# Configuration_Logic.net
KiCad netlist of a schematic drawn in Altium Designer
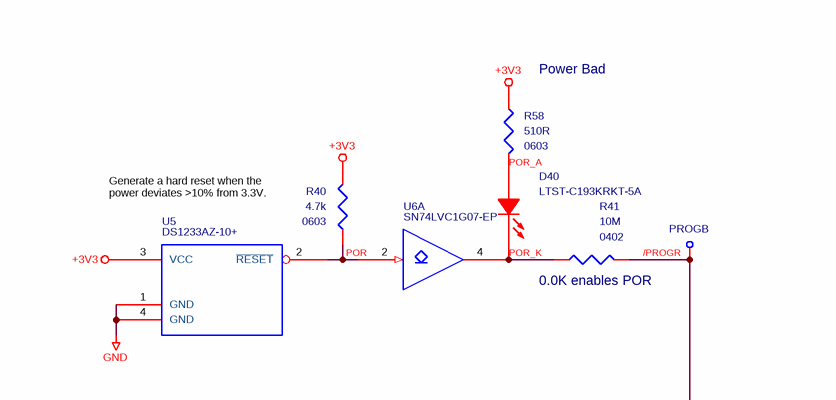
[diagram p0: Configuration_Logic.SchDoc, top left]
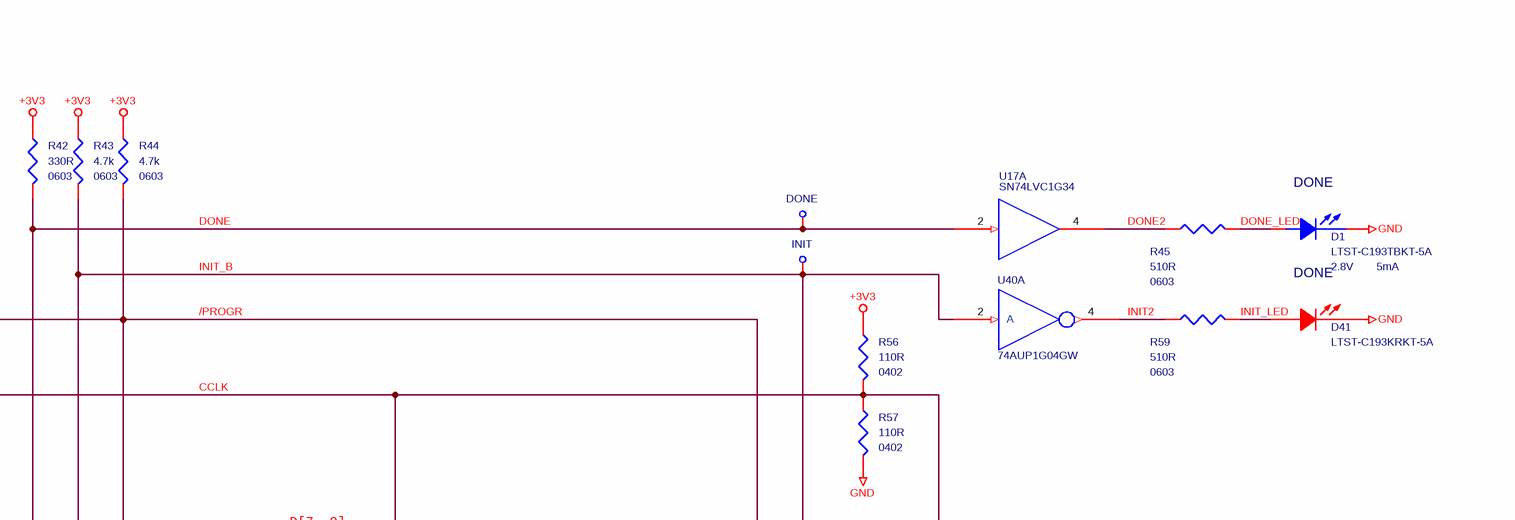
[diagram p1: Configuration_Logic.SchDoc, top right]
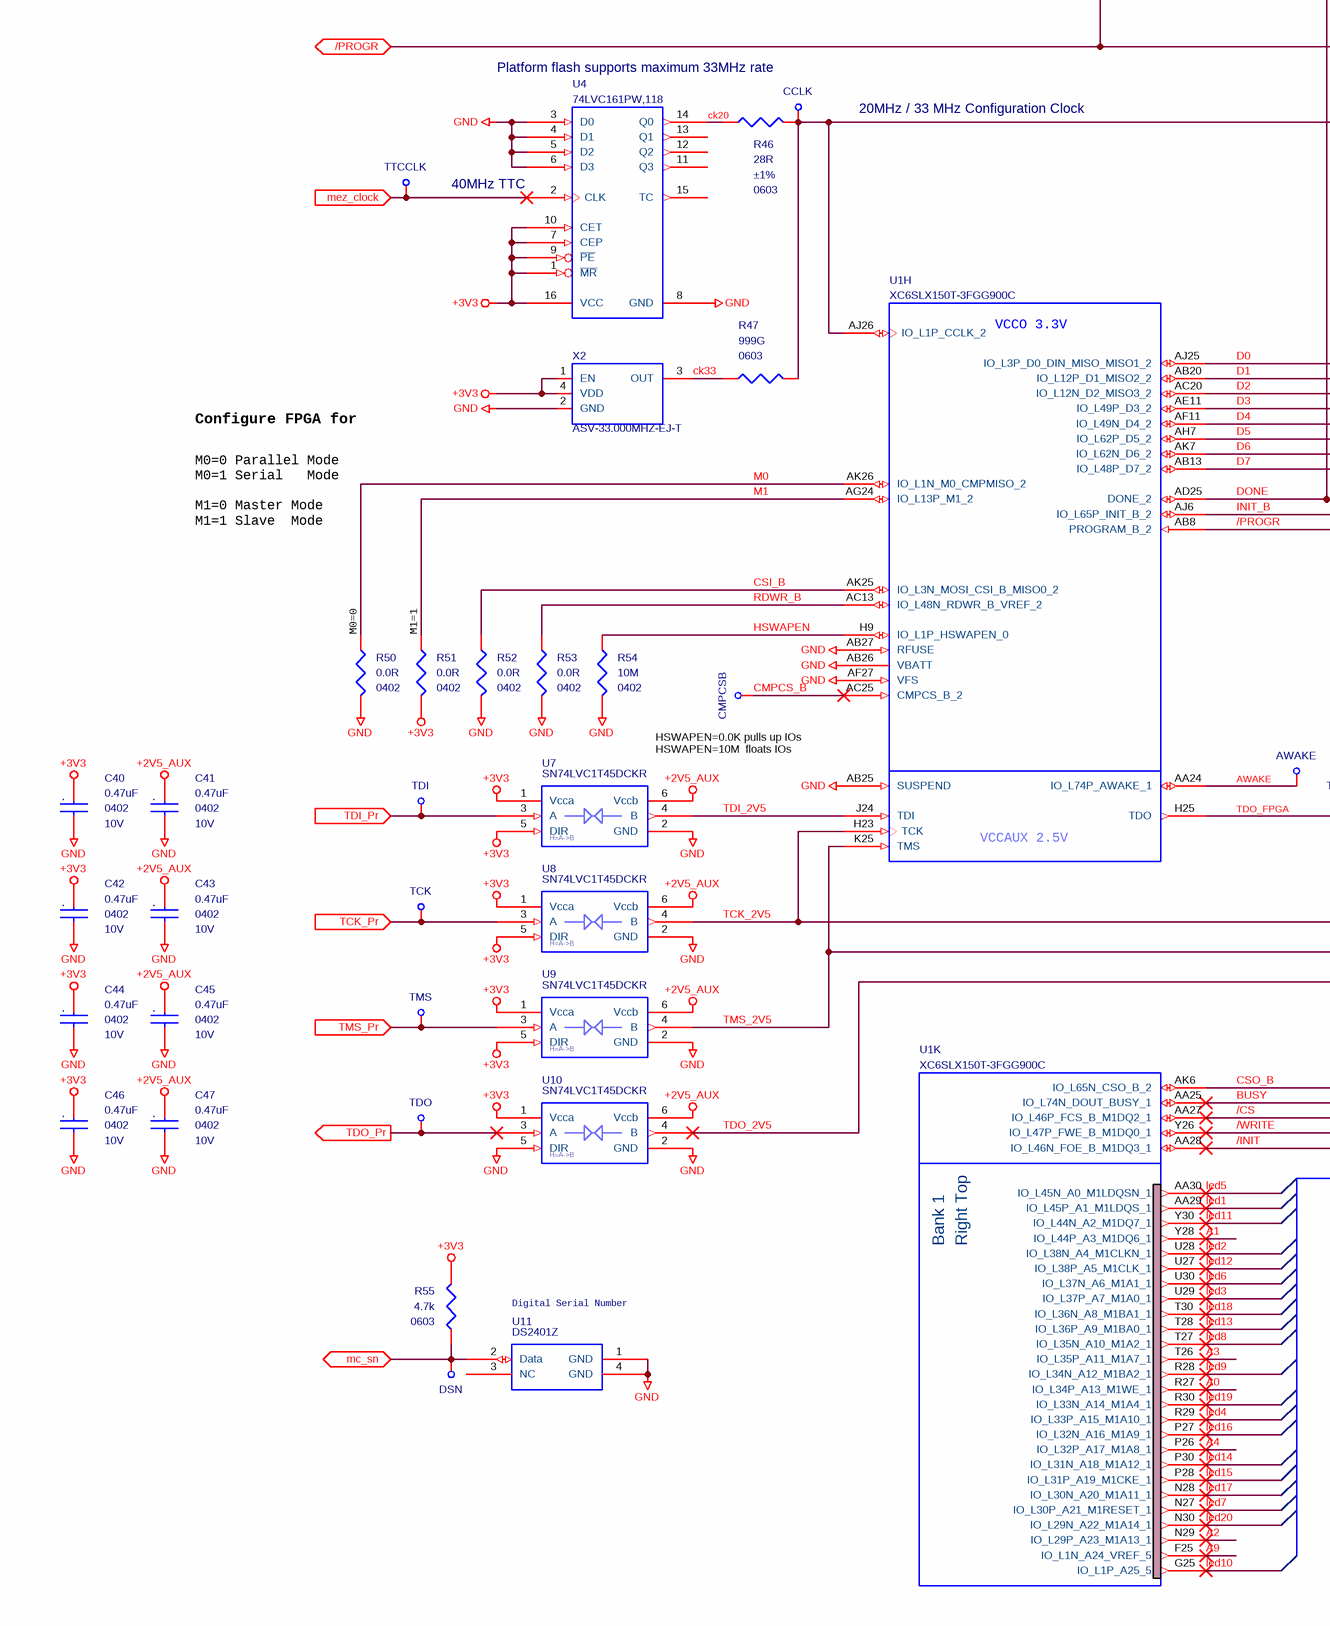
[diagram p2: Configuration_Logic.SchDoc, bottom left]
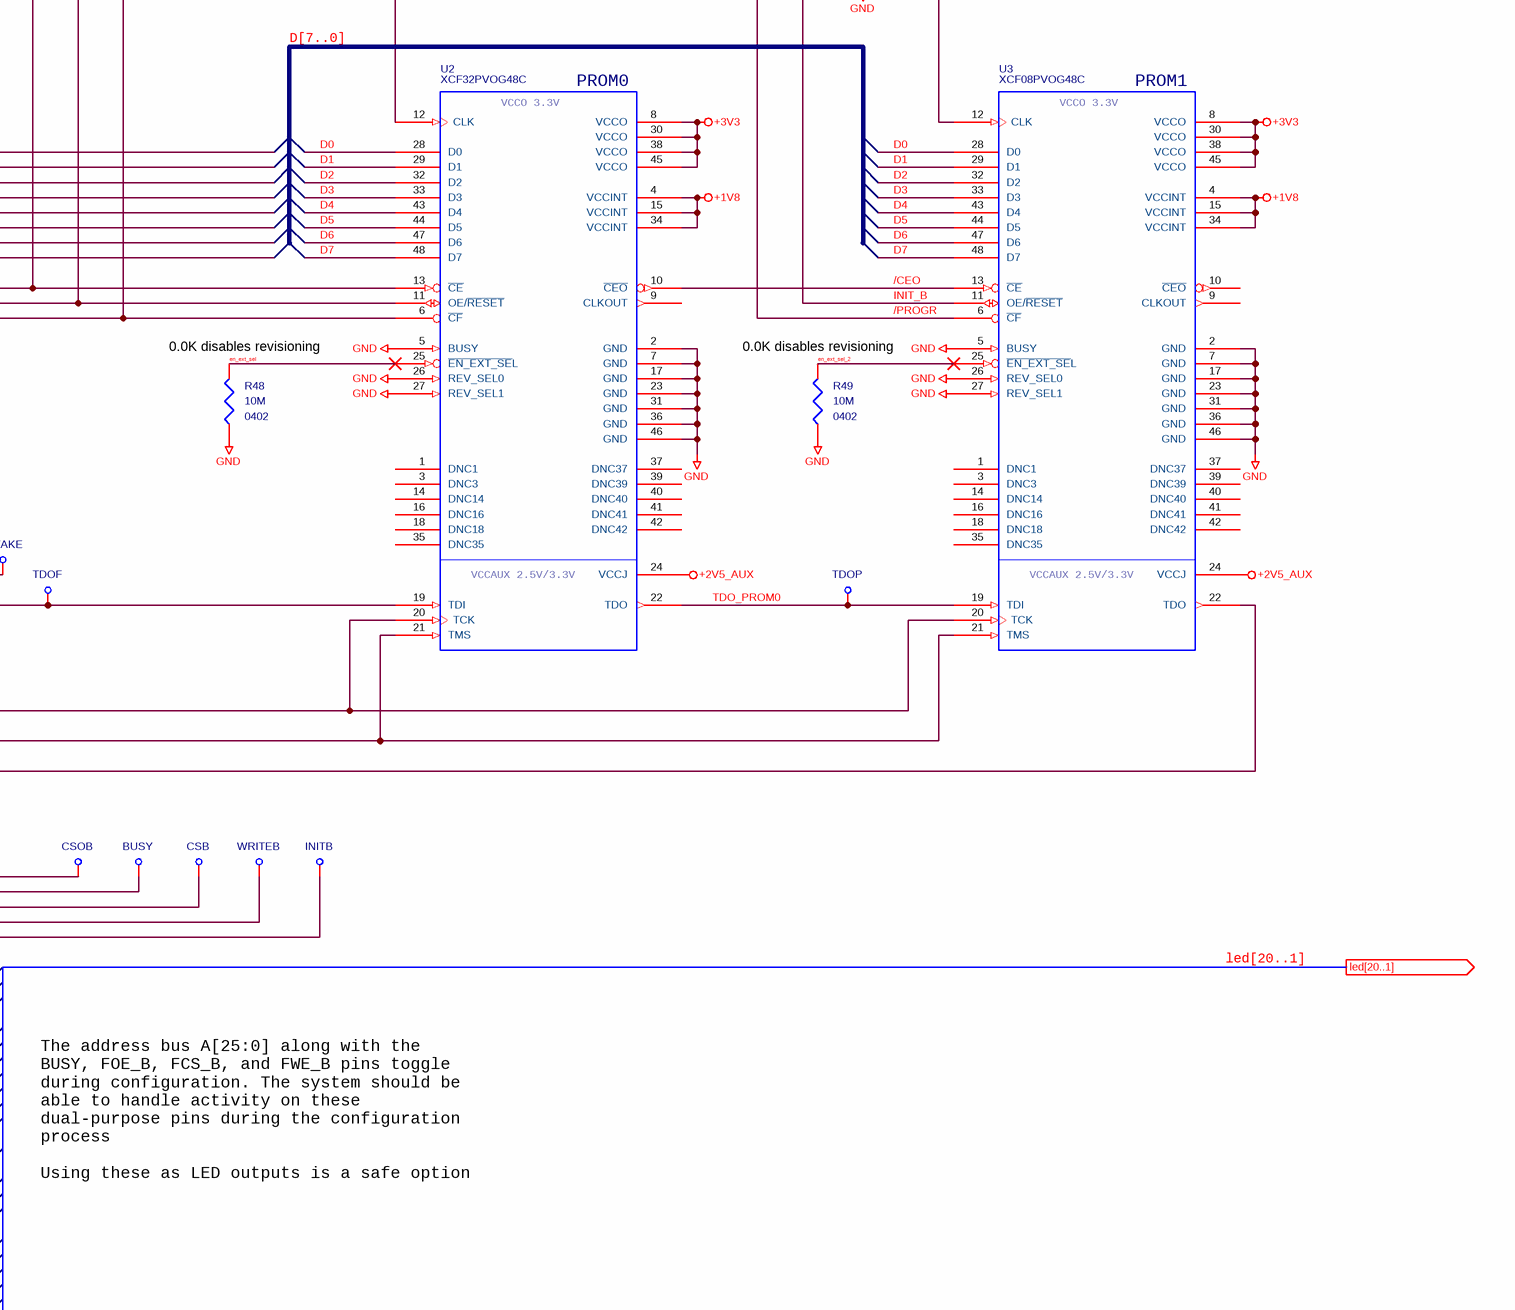
[diagram p3: Configuration_Logic.SchDoc, bottom right]

(export (version "E")
  (design (tool "Eeschema 10.0.6"))
  (components
    (comp (ref "AWAKE")
      (value "Test Point Via")
      (footprint "MC_S6/TH/TPVIA")
      (libsource (lib "ALCT_MEZ_SPARTAN6_Library") (part "TPVIA"))
    )
    (comp (ref "BUSY")
      (value "Test Point Via")
      (footprint "MC_S6/TH/TPVIA")
      (libsource (lib "ALCT_MEZ_SPARTAN6_Library") (part "TPVIA"))
    )
    (comp (ref "C40")
      (value "0.47uF")
      (footprint "MC_S6/SM/C_0402_IPC")
      (description "CAP CER 0.47UF 10V X5R 0402")
      (fields
        (field (name "MANUFACTURER") "Murata Electronics North America")
        (field (name "MANUFACTURER PART NUMBER") "GRM155R61A474KE15J")
        (field (name "VOLTAGE - RATED") "10V")
        (field (name "PACKAGE") "0402")
      )
      (libsource (lib "ALCT_MEZ_SPARTAN6_Library") (part "GRM155R61A474KE15J"))
    )
    (comp (ref "C41")
      (value "0.47uF")
      (footprint "MC_S6/SM/C_0402_IPC")
      (description "CAP CER 0.47UF 10V X5R 0402")
      (fields
        (field (name "MANUFACTURER") "Murata Electronics North America")
        (field (name "MANUFACTURER PART NUMBER") "GRM155R61A474KE15J")
        (field (name "VOLTAGE - RATED") "10V")
        (field (name "PACKAGE") "0402")
      )
      (libsource (lib "ALCT_MEZ_SPARTAN6_Library") (part "GRM155R61A474KE15J"))
    )
    (comp (ref "C42")
      (value "0.47uF")
      (footprint "MC_S6/SM/C_0402_IPC")
      (description "CAP CER 0.47UF 10V X5R 0402")
      (fields
        (field (name "MANUFACTURER") "Murata Electronics North America")
        (field (name "MANUFACTURER PART NUMBER") "GRM155R61A474KE15J")
        (field (name "VOLTAGE - RATED") "10V")
        (field (name "PACKAGE") "0402")
      )
      (libsource (lib "ALCT_MEZ_SPARTAN6_Library") (part "GRM155R61A474KE15J"))
    )
    (comp (ref "C43")
      (value "0.47uF")
      (footprint "MC_S6/SM/C_0402_IPC")
      (description "CAP CER 0.47UF 10V X5R 0402")
      (fields
        (field (name "MANUFACTURER") "Murata Electronics North America")
        (field (name "MANUFACTURER PART NUMBER") "GRM155R61A474KE15J")
        (field (name "VOLTAGE - RATED") "10V")
        (field (name "PACKAGE") "0402")
      )
      (libsource (lib "ALCT_MEZ_SPARTAN6_Library") (part "GRM155R61A474KE15J"))
    )
    (comp (ref "C44")
      (value "0.47uF")
      (footprint "MC_S6/SM/C_0402_IPC")
      (description "CAP CER 0.47UF 10V X5R 0402")
      (fields
        (field (name "MANUFACTURER") "Murata Electronics North America")
        (field (name "MANUFACTURER PART NUMBER") "GRM155R61A474KE15J")
        (field (name "VOLTAGE - RATED") "10V")
        (field (name "PACKAGE") "0402")
      )
      (libsource (lib "ALCT_MEZ_SPARTAN6_Library") (part "GRM155R61A474KE15J"))
    )
    (comp (ref "C45")
      (value "0.47uF")
      (footprint "MC_S6/SM/C_0402_IPC")
      (description "CAP CER 0.47UF 10V X5R 0402")
      (fields
        (field (name "MANUFACTURER") "Murata Electronics North America")
        (field (name "MANUFACTURER PART NUMBER") "GRM155R61A474KE15J")
        (field (name "VOLTAGE - RATED") "10V")
        (field (name "PACKAGE") "0402")
      )
      (libsource (lib "ALCT_MEZ_SPARTAN6_Library") (part "GRM155R61A474KE15J"))
    )
    (comp (ref "C46")
      (value "0.47uF")
      (footprint "MC_S6/SM/C_0402_IPC")
      (description "CAP CER 0.47UF 10V X5R 0402")
      (fields
        (field (name "MANUFACTURER") "Murata Electronics North America")
        (field (name "MANUFACTURER PART NUMBER") "GRM155R61A474KE15J")
        (field (name "VOLTAGE - RATED") "10V")
        (field (name "PACKAGE") "0402")
      )
      (libsource (lib "ALCT_MEZ_SPARTAN6_Library") (part "GRM155R61A474KE15J"))
    )
    (comp (ref "C47")
      (value "0.47uF")
      (footprint "MC_S6/SM/C_0402_IPC")
      (description "CAP CER 0.47UF 10V X5R 0402")
      (fields
        (field (name "MANUFACTURER") "Murata Electronics North America")
        (field (name "MANUFACTURER PART NUMBER") "GRM155R61A474KE15J")
        (field (name "VOLTAGE - RATED") "10V")
        (field (name "PACKAGE") "0402")
      )
      (libsource (lib "ALCT_MEZ_SPARTAN6_Library") (part "GRM155R61A474KE15J"))
    )
    (comp (ref "CCLK")
      (value "Test Point Via")
      (footprint "MC_S6/TH/TPVIA")
      (libsource (lib "ALCT_MEZ_SPARTAN6_Library") (part "TPVIA"))
    )
    (comp (ref "CMPCSB")
      (value "Test Point Via")
      (footprint "MC_S6/TH/TPVIA")
      (libsource (lib "ALCT_MEZ_SPARTAN6_Library") (part "TPVIA"))
    )
    (comp (ref "CSB")
      (value "Test Point Via")
      (footprint "MC_S6/TH/TPVIA")
      (libsource (lib "ALCT_MEZ_SPARTAN6_Library") (part "TPVIA"))
    )
    (comp (ref "CSOB")
      (value "Test Point Via")
      (footprint "MC_S6/TH/TPVIA")
      (libsource (lib "ALCT_MEZ_SPARTAN6_Library") (part "TPVIA"))
    )
    (comp (ref "D1")
      (value "LTST-C193TBKT-5A")
      (footprint "MC_S6/SM/LED_0603")
      (description "LED BLUE CLEAR 0603 SMD")
      (fields
        (field (name "MANUFACTURER") "Lite-On Inc.")
        (field (name "VOLTAGE - FORWARD (VF) (TYP)") "2.8V")
        (field (name "CURRENT - TEST") "5mA")
      )
      (libsource (lib "ALCT_MEZ_SPARTAN6_Library") (part "LTST-C193TBKT-5A"))
    )
    (comp (ref "D40")
      (value "LTST-C193KRKT-5A")
      (footprint "MC_S6/SM/LED_0603")
      (description "LED RED CLEAR 0603 SMD")
      (fields (field (name "MANUFACTURER") "Lite-On Inc."))
      (libsource (lib "ALCT_MEZ_SPARTAN6_Library") (part "LTST-C193KRKT-5A"))
    )
    (comp (ref "D41")
      (value "LTST-C193KRKT-5A")
      (footprint "MC_S6/SM/LED_0603")
      (description "LED RED CLEAR 0603 SMD")
      (fields (field (name "MANUFACTURER") "Lite-On Inc."))
      (libsource (lib "ALCT_MEZ_SPARTAN6_Library") (part "LTST-C193KRKT-5A"))
    )
    (comp (ref "DONE")
      (value "Test Point Via")
      (footprint "MC_S6/TH/TPVIA")
      (libsource (lib "ALCT_MEZ_SPARTAN6_Library") (part "TPVIA"))
    )
    (comp (ref "DSN")
      (value "Test Point Via")
      (footprint "MC_S6/TH/TPVIA")
      (libsource (lib "ALCT_MEZ_SPARTAN6_Library") (part "TPVIA"))
    )
    (comp (ref "INIT")
      (value "Test Point Via")
      (footprint "MC_S6/TH/TPVIA")
      (libsource (lib "ALCT_MEZ_SPARTAN6_Library") (part "TPVIA"))
    )
    (comp (ref "INITB")
      (value "Test Point Via")
      (footprint "MC_S6/TH/TPVIA")
      (libsource (lib "ALCT_MEZ_SPARTAN6_Library") (part "TPVIA"))
    )
    (comp (ref "PROGB")
      (value "Test Point Via")
      (footprint "MC_S6/TH/TPVIA")
      (libsource (lib "ALCT_MEZ_SPARTAN6_Library") (part "TPVIA"))
    )
    (comp (ref "R40")
      (value "4.7k")
      (footprint "MC_S6/SM/R_0603_IPC")
      (description "RES SMD 4.7K OHM 1% 1/10W 0603")
      (fields
        (field (name "MANUFACTURER") "Bourns Inc.")
        (field (name "MANUFACTURER PART NUMBER") "CR0603-FX-4701ELF")
        (field (name "SUPPLIER DEVICE PACKAGE") "0603")
      )
      (libsource (lib "ALCT_MEZ_SPARTAN6_Library") (part "CR0603-FX-4701ELF"))
    )
    (comp (ref "R41")
      (value "10M")
      (footprint "MC_S6/SM/C_0402_IPC")
      (description "RES SMD 10M OHM 5% 1/10W 0402")
      (fields
        (field (name "TOLERANCE") "±5%")
        (field (name "MANUFACTURER") "Panasonic Electronic Components")
        (field (name "SUPPLIER DEVICE PACKAGE") "0402")
      )
      (libsource (lib "ALCT_MEZ_SPARTAN6_Library") (part "ERJ-2GEJ106X"))
    )
    (comp (ref "R42")
      (value "330R")
      (footprint "MC_S6/SM/R_0603_IPC")
      (description "RES SMD 330 OHM 1% 1/10W 0603")
      (fields
        (field (name "TOLERANCE") "±1%")
        (field (name "MANUFACTURER") "Bourns Inc.")
        (field (name "SUPPLIER DEVICE PACKAGE") "0603")
      )
      (libsource (lib "ALCT_MEZ_SPARTAN6_Library") (part "CR0603-FX-3300ELF"))
    )
    (comp (ref "R43")
      (value "4.7k")
      (footprint "MC_S6/SM/R_0603_IPC")
      (description "RES SMD 4.7K OHM 1% 1/10W 0603")
      (fields
        (field (name "TOLERANCE") "±1%")
        (field (name "MANUFACTURER") "Bourns Inc.")
        (field (name "SUPPLIER DEVICE PACKAGE") "0603")
      )
      (libsource (lib "ALCT_MEZ_SPARTAN6_Library") (part "CR0603-FX-4701ELF"))
    )
    (comp (ref "R44")
      (value "4.7k")
      (footprint "MC_S6/SM/R_0603_IPC")
      (description "RES SMD 4.7K OHM 1% 1/10W 0603")
      (fields
        (field (name "TOLERANCE") "±1%")
        (field (name "MANUFACTURER") "Bourns Inc.")
        (field (name "SUPPLIER DEVICE PACKAGE") "0603")
      )
      (libsource (lib "ALCT_MEZ_SPARTAN6_Library") (part "CR0603-FX-4701ELF"))
    )
    (comp (ref "R45")
      (value "510R")
      (footprint "MC_S6/SM/R_0603_IPC")
      (description "RES SMD 510 OHM 1% 1/10W 0603")
      (fields
        (field (name "TOLERANCE") "±1%")
        (field (name "MANUFACTURER") "Bourns Inc.")
        (field (name "SUPPLIER DEVICE PACKAGE") "0603")
      )
      (libsource (lib "ALCT_MEZ_SPARTAN6_Library") (part "CR0603-FX-5100ELF"))
    )
    (comp (ref "R46")
      (value "28R")
      (footprint "MC_S6/SM/R_0603_IPC")
      (description "RES SMD 28 OHM 1% 1/10W 0603")
      (fields
        (field (name "TOLERANCE") "±1%")
        (field (name "MANUFACTURER") "Panasonic Electronic Components")
        (field (name "MANUFACTURER PART NUMBER") "ERJ-3EKF28R0V")
        (field (name "SUPPLIER DEVICE PACKAGE") "0603")
      )
      (libsource (lib "ALCT_MEZ_SPARTAN6_Library") (part "ERJ-3EKF28R0V"))
    )
    (comp (ref "R47")
      (value "999G")
      (footprint "MC_S6/SM/R_0603_IPC")
      (description "RES SMD 999G OHM 5% 1/10W 0603")
      (fields
        (field (name "MANUFACTURER PART NUMBER") "Do Not Place")
        (field (name "SUPPLIER DEVICE PACKAGE") "0603")
      )
      (libsource (lib "ALCT_MEZ_SPARTAN6_Library") (part "RES999G 0603"))
    )
    (comp (ref "R48")
      (value "10M")
      (footprint "MC_S6/SM/C_0402_IPC")
      (description "RES SMD 10M OHM 5% 1/10W 0402")
      (fields
        (field (name "TOLERANCE") "±5%")
        (field (name "MANUFACTURER") "Panasonic Electronic Components")
        (field (name "SUPPLIER DEVICE PACKAGE") "0402")
      )
      (libsource (lib "ALCT_MEZ_SPARTAN6_Library") (part "ERJ-2GEJ106X"))
    )
    (comp (ref "R49")
      (value "10M")
      (footprint "MC_S6/SM/C_0402_IPC")
      (description "RES SMD 10M OHM 5% 1/10W 0402")
      (fields
        (field (name "TOLERANCE") "±5%")
        (field (name "MANUFACTURER") "Panasonic Electronic Components")
        (field (name "SUPPLIER DEVICE PACKAGE") "0402")
      )
      (libsource (lib "ALCT_MEZ_SPARTAN6_Library") (part "ERJ-2GEJ106X"))
    )
    (comp (ref "R50")
      (value "0.0R")
      (footprint "MC_S6/SM/R_0402_IPC")
      (description "RES SMD 0.0OHM JUMPER 1/10W 0402")
      (fields
        (field (name "TOLERANCE") "Jumper")
        (field (name "MANUFACTURER") "Panasonic Electronic Components")
        (field (name "SUPPLIER DEVICE PACKAGE") "0402")
      )
      (libsource (lib "ALCT_MEZ_SPARTAN6_Library") (part "ERJ-2GE0R00X"))
    )
    (comp (ref "R51")
      (value "0.0R")
      (footprint "MC_S6/SM/R_0402_IPC")
      (description "RES SMD 0.0OHM JUMPER 1/10W 0402")
      (fields
        (field (name "TOLERANCE") "Jumper")
        (field (name "MANUFACTURER") "Panasonic Electronic Components")
        (field (name "SUPPLIER DEVICE PACKAGE") "0402")
      )
      (libsource (lib "ALCT_MEZ_SPARTAN6_Library") (part "ERJ-2GE0R00X"))
    )
    (comp (ref "R52")
      (value "0.0R")
      (footprint "MC_S6/SM/R_0402_IPC")
      (description "RES SMD 0.0OHM JUMPER 1/10W 0402")
      (fields
        (field (name "TOLERANCE") "Jumper")
        (field (name "MANUFACTURER") "Panasonic Electronic Components")
        (field (name "SUPPLIER DEVICE PACKAGE") "0402")
      )
      (libsource (lib "ALCT_MEZ_SPARTAN6_Library") (part "ERJ-2GE0R00X"))
    )
    (comp (ref "R53")
      (value "0.0R")
      (footprint "MC_S6/SM/R_0402_IPC")
      (description "RES SMD 0.0OHM JUMPER 1/10W 0402")
      (fields
        (field (name "TOLERANCE") "Jumper")
        (field (name "MANUFACTURER") "Panasonic Electronic Components")
        (field (name "SUPPLIER DEVICE PACKAGE") "0402")
      )
      (libsource (lib "ALCT_MEZ_SPARTAN6_Library") (part "ERJ-2GE0R00X"))
    )
    (comp (ref "R54")
      (value "10M")
      (footprint "MC_S6/SM/C_0402_IPC")
      (description "RES SMD 10M OHM 5% 1/10W 0402")
      (fields
        (field (name "TOLERANCE") "±5%")
        (field (name "MANUFACTURER") "Panasonic Electronic Components")
        (field (name "SUPPLIER DEVICE PACKAGE") "0402")
      )
      (libsource (lib "ALCT_MEZ_SPARTAN6_Library") (part "ERJ-2GEJ106X"))
    )
    (comp (ref "R55")
      (value "4.7k")
      (footprint "MC_S6/SM/R_0603_IPC")
      (description "RES SMD 4.7K OHM 1% 1/10W 0603")
      (fields
        (field (name "MANUFACTURER") "Bourns Inc.")
        (field (name "MANUFACTURER PART NUMBER") "CR0603-FX-4701ELF")
        (field (name "SUPPLIER DEVICE PACKAGE") "0603")
      )
      (libsource (lib "ALCT_MEZ_SPARTAN6_Library") (part "CR0603-FX-4701ELF"))
    )
    (comp (ref "R56")
      (value "110R")
      (footprint "MC_S6/SM/R_0402_IPC")
      (description "RES SMD 110 OHM 1% 1/10W 0402")
      (fields
        (field (name "MANUFACTURER") "Panasonic Electronic Components")
        (field (name "MANUFACTURER PART NUMBER") "ERJ-2RKF1100X")
        (field (name "SUPPLIER DEVICE PACKAGE") "0402")
      )
      (libsource (lib "ALCT_MEZ_SPARTAN6_Library") (part "ERJ-2RKF1100X"))
    )
    (comp (ref "R57")
      (value "110R")
      (footprint "MC_S6/SM/R_0402_IPC")
      (description "RES SMD 110 OHM 1% 1/10W 0402")
      (fields
        (field (name "MANUFACTURER") "Panasonic Electronic Components")
        (field (name "MANUFACTURER PART NUMBER") "ERJ-2RKF1100X")
        (field (name "SUPPLIER DEVICE PACKAGE") "0402")
      )
      (libsource (lib "ALCT_MEZ_SPARTAN6_Library") (part "ERJ-2RKF1100X"))
    )
    (comp (ref "R58")
      (value "510R")
      (footprint "MC_S6/SM/R_0603_IPC")
      (description "RES SMD 510 OHM 1% 1/10W 0603")
      (fields
        (field (name "TOLERANCE") "±1%")
        (field (name "MANUFACTURER") "Bourns Inc.")
        (field (name "SUPPLIER DEVICE PACKAGE") "0603")
      )
      (libsource (lib "ALCT_MEZ_SPARTAN6_Library") (part "CR0603-FX-5100ELF"))
    )
    (comp (ref "R59")
      (value "510R")
      (footprint "MC_S6/SM/R_0603_IPC")
      (description "RES SMD 510 OHM 1% 1/10W 0603")
      (fields
        (field (name "TOLERANCE") "±1%")
        (field (name "MANUFACTURER") "Bourns Inc.")
        (field (name "SUPPLIER DEVICE PACKAGE") "0603")
      )
      (libsource (lib "ALCT_MEZ_SPARTAN6_Library") (part "CR0603-FX-5100ELF"))
    )
    (comp (ref "TCK")
      (value "Test Point Via")
      (footprint "MC_S6/TH/TPVIA")
      (libsource (lib "ALCT_MEZ_SPARTAN6_Library") (part "TPVIA"))
    )
    (comp (ref "TDI")
      (value "Test Point Via")
      (footprint "MC_S6/TH/TPVIA")
      (libsource (lib "ALCT_MEZ_SPARTAN6_Library") (part "TPVIA"))
    )
    (comp (ref "TDO")
      (value "Test Point Via")
      (footprint "MC_S6/TH/TPVIA")
      (libsource (lib "ALCT_MEZ_SPARTAN6_Library") (part "TPVIA"))
    )
    (comp (ref "TDOF")
      (value "Test Point Via")
      (footprint "MC_S6/TH/TPVIA")
      (libsource (lib "ALCT_MEZ_SPARTAN6_Library") (part "TPVIA"))
    )
    (comp (ref "TDOP")
      (value "Test Point Via")
      (footprint "MC_S6/TH/TPVIA")
      (libsource (lib "ALCT_MEZ_SPARTAN6_Library") (part "TPVIA"))
    )
    (comp (ref "TMS")
      (value "Test Point Via")
      (footprint "MC_S6/TH/TPVIA")
      (libsource (lib "ALCT_MEZ_SPARTAN6_Library") (part "TPVIA"))
    )
    (comp (ref "TTCCLK")
      (value "Test Point Via")
      (footprint "MC_S6/TH/TPVIA")
      (libsource (lib "ALCT_MEZ_SPARTAN6_Library") (part "TPVIA"))
    )
    (comp (ref "U1")
      (value "XC6SLX150T-3FGG900C")
      (footprint "MC_S6/BGA/FGG900")
      (fields (field (name "MANUFACTURER") "Xilinx Inc."))
      (libsource (lib "ALCT_MEZ_SPARTAN6_Library") (part "XC6SLX150T-3FGG900C"))
    )
    (comp (ref "U2")
      (value "XCF32PVOG48C")
      (footprint "MC_S6/SM/VOG48")
      (description "IC PROM SRL/PAR 1.8V 32M 48TSOP")
      (fields (field (name "MANUFACTURER") "Xilinx Inc."))
      (libsource (lib "ALCT_MEZ_SPARTAN6_Library") (part "XCF32PVOG48C"))
    )
    (comp (ref "U3")
      (value "XCF08PVOG48C")
      (footprint "MC_S6/SM/VOG48")
      (description "IC PROM SRL/PAR 1.8V 08M 48TSOP")
      (fields (field (name "MANUFACTURER") "Xilinx Inc."))
      (libsource (lib "ALCT_MEZ_SPARTAN6_Library") (part "XCF08PVOG48C"))
    )
    (comp (ref "U4")
      (value "74LVC161PW,118")
      (footprint "MC_S6/SM/TSSOP16")
      (description "IC SYNC 4BIT BIN COUNTER 16TSSOP")
      (fields (field (name "MANUFACTURER") "NXP USA Inc."))
      (libsource (lib "ALCT_MEZ_SPARTAN6_Library") (part "74LVC161PW"))
    )
    (comp (ref "U5")
      (value "DS1233AZ-10+")
      (footprint "MC_S6/SM/SOT223_1243")
      (description "IC POR 2.88V 10% SOT223")
      (fields
        (field (name "MANUFACTURER") "Maxim Integrated")
        (field (name "MANUFACTURER PART NUMBER") "DS1233AZ-10+T&R")
      )
      (libsource (lib "ALCT_MEZ_SPARTAN6_Library") (part "DS1233AZ-10+"))
    )
    (comp (ref "U6")
      (value "SN74LVC1G07-EP")
      (footprint "SOT353-1")
      (description "IC BUFF/DVR NON-INVERT Open Drain SC70-5")
      (fields
        (field (name "MANUFACTURER") "Texas Instruments")
        (field (name "MANUFACTURER PART NUMBER") "SN74LVC1G07MDCKREP")
      )
      (libsource (lib "ALCT_MEZ_SPARTAN6_Library") (part "SN74LVC1G07-EP"))
    )
    (comp (ref "U7")
      (value "SN74LVC1T45DCKR")
      (footprint "MC_S6/SM/SOT_SC70_DCK6")
      (description "IC BUS TRANSCVR TRI-ST SC70-6")
      (fields (field (name "MANUFACTURER") "Texas Instruments"))
      (libsource (lib "ALCT_MEZ_SPARTAN6_Library") (part "SN74LVC1T45-EP-ALCT_1"))
    )
    (comp (ref "U8")
      (value "SN74LVC1T45DCKR")
      (footprint "MC_S6/SM/SOT_SC70_DCK6")
      (description "IC BUS TRANSCVR TRI-ST SC70-6")
      (fields (field (name "MANUFACTURER") "Texas Instruments"))
      (libsource (lib "ALCT_MEZ_SPARTAN6_Library") (part "SN74LVC1T45-EP-ALCT_1"))
    )
    (comp (ref "U9")
      (value "SN74LVC1T45DCKR")
      (footprint "MC_S6/SM/SOT_SC70_DCK6")
      (description "IC BUS TRANSCVR TRI-ST SC70-6")
      (fields (field (name "MANUFACTURER") "Texas Instruments"))
      (libsource (lib "ALCT_MEZ_SPARTAN6_Library") (part "SN74LVC1T45-EP-ALCT_1"))
    )
    (comp (ref "U10")
      (value "SN74LVC1T45DCKR")
      (footprint "MC_S6/SM/SOT_SC70_DCK6")
      (description "IC BUS TRANSCVR TRI-ST SC70-6")
      (fields (field (name "MANUFACTURER") "Texas Instruments"))
      (libsource (lib "ALCT_MEZ_SPARTAN6_Library") (part "SN74LVC1T45-EP-ALCT_1"))
    )
    (comp (ref "U11")
      (value "DS2401Z")
      (footprint "MC_S6/SM/SOT223_1243")
      (description "IC Digital Serial Number")
      (fields
        (field (name "MANUFACTURER") "Maxim Integrated")
        (field (name "MANUFACTURER PART NUMBER") "DS2401Z+T&R")
      )
      (libsource (lib "ALCT_MEZ_SPARTAN6_Library") (part "DS2401_sot223"))
    )
    (comp (ref "U17")
      (value "SN74LVC1G34")
      (footprint "MC_S6/SM/SOT_553_DRL5")
      (description "IC BUFFER NON-INVERT SOT5")
      (fields
        (field (name "MANUFACTURER") "Texas Instruments")
        (field (name "MANUFACTURER PART NUMBER") "SN74LVC1G34DRLR")
      )
      (libsource (lib "ALCT_MEZ_SPARTAN6_Library") (part "SN74LVC1G34DRLR"))
    )
    (comp (ref "U40")
      (value "74AUP1G04GW")
      (footprint "SOT353-1")
      (description "IC INVERTER LP 5TSSOP")
      (fields
        (field (name "MANUFACTURER") "Nexperia USA Inc.")
        (field (name "MANUFACTURER PART NUMBER") "74AUP1G04GW,125")
      )
      (libsource (lib "ALCT_MEZ_SPARTAN6_Library") (part "74AUP1G04GW"))
    )
    (comp (ref "WRITEB")
      (value "Test Point Via")
      (footprint "MC_S6/TH/TPVIA")
      (libsource (lib "ALCT_MEZ_SPARTAN6_Library") (part "TPVIA"))
    )
    (comp (ref "X2")
      (value "ASV-33.000MHZ-EJ-T")
      (footprint "MC_S6/SM/XTAL-7x5.08")
      (description "XTAL, 33MHz, CMOS")
      (fields (field (name "MANUFACTURER") "Abracon LLC"))
      (libsource (lib "ALCT_MEZ_SPARTAN6_Library") (part "ASV-33.000MHZ-EJ-T"))
    )
  )
  (nets
    (net (code "1") (name "+1V8") (class "Default")
      (node (ref "U2") (pin "15") (pinfunction "VCCINT_15") (pintype "power_in"))
      (node (ref "U2") (pin "34") (pinfunction "VCCINT_34") (pintype "power_in"))
      (node (ref "U2") (pin "4") (pinfunction "VCCINT_4") (pintype "power_in"))
      (node (ref "U3") (pin "15") (pinfunction "VCCINT_15") (pintype "power_in"))
      (node (ref "U3") (pin "34") (pinfunction "VCCINT_34") (pintype "power_in"))
      (node (ref "U3") (pin "4") (pinfunction "VCCINT_4") (pintype "power_in"))
    )
    (net (code "2") (name "+2V5_AUX") (class "Default")
      (node (ref "C41") (pin "1") (pinfunction "1_1") (pintype "passive"))
      (node (ref "C43") (pin "1") (pinfunction "1_1") (pintype "passive"))
      (node (ref "C45") (pin "1") (pinfunction "1_1") (pintype "passive"))
      (node (ref "C47") (pin "1") (pinfunction "1_1") (pintype "passive"))
      (node (ref "U10") (pin "6") (pinfunction "Vccb_6") (pintype "power_in"))
      (node (ref "U2") (pin "24") (pinfunction "VCCJ_24") (pintype "power_in"))
      (node (ref "U3") (pin "24") (pinfunction "VCCJ_24") (pintype "power_in"))
      (node (ref "U7") (pin "6") (pinfunction "Vccb_6") (pintype "power_in"))
      (node (ref "U8") (pin "6") (pinfunction "Vccb_6") (pintype "power_in"))
      (node (ref "U9") (pin "6") (pinfunction "Vccb_6") (pintype "power_in"))
    )
    (net (code "3") (name "+3V3") (class "Default")
      (node (ref "C40") (pin "1") (pinfunction "1_1") (pintype "passive"))
      (node (ref "C42") (pin "1") (pinfunction "1_1") (pintype "passive"))
      (node (ref "C44") (pin "1") (pinfunction "1_1") (pintype "passive"))
      (node (ref "C46") (pin "1") (pinfunction "1_1") (pintype "passive"))
      (node (ref "R40") (pin "1") (pinfunction "1_1") (pintype "passive"))
      (node (ref "R42") (pin "1") (pinfunction "1_1") (pintype "passive"))
      (node (ref "R43") (pin "1") (pinfunction "1_1") (pintype "passive"))
      (node (ref "R44") (pin "1") (pinfunction "1_1") (pintype "passive"))
      (node (ref "R51") (pin "2") (pinfunction "2_2") (pintype "passive"))
      (node (ref "R55") (pin "1") (pinfunction "1_1") (pintype "passive"))
      (node (ref "R56") (pin "1") (pinfunction "1_1") (pintype "passive"))
      (node (ref "R58") (pin "1") (pinfunction "1_1") (pintype "passive"))
      (node (ref "U10") (pin "1") (pinfunction "Vcca_1") (pintype "power_in"))
      (node (ref "U2") (pin "30") (pinfunction "VCCO_30") (pintype "power_in"))
      (node (ref "U2") (pin "38") (pinfunction "VCCO_38") (pintype "power_in"))
      (node (ref "U2") (pin "45") (pinfunction "VCCO_45") (pintype "power_in"))
      (node (ref "U2") (pin "8") (pinfunction "VCCO_8") (pintype "power_in"))
      (node (ref "U3") (pin "30") (pinfunction "VCCO_30") (pintype "power_in"))
      (node (ref "U3") (pin "38") (pinfunction "VCCO_38") (pintype "power_in"))
      (node (ref "U3") (pin "45") (pinfunction "VCCO_45") (pintype "power_in"))
      (node (ref "U3") (pin "8") (pinfunction "VCCO_8") (pintype "power_in"))
      (node (ref "U4") (pin "1") (pinfunction "~{MR}_1") (pintype "input"))
      (node (ref "U4") (pin "10") (pinfunction "CET_10") (pintype "input"))
      (node (ref "U4") (pin "16") (pinfunction "VCC_16") (pintype "power_in"))
      (node (ref "U4") (pin "7") (pinfunction "CEP_7") (pintype "input"))
      (node (ref "U4") (pin "9") (pinfunction "~{PE}_9") (pintype "input"))
      (node (ref "U5") (pin "3") (pinfunction "VCC_3") (pintype "power_in"))
      (node (ref "U7") (pin "1") (pinfunction "Vcca_1") (pintype "power_in"))
      (node (ref "U7") (pin "5") (pinfunction "DIR_5") (pintype "input"))
      (node (ref "U8") (pin "1") (pinfunction "Vcca_1") (pintype "power_in"))
      (node (ref "U8") (pin "5") (pinfunction "DIR_5") (pintype "input"))
      (node (ref "U9") (pin "1") (pinfunction "Vcca_1") (pintype "power_in"))
      (node (ref "U9") (pin "5") (pinfunction "DIR_5") (pintype "input"))
      (node (ref "X2") (pin "1") (pinfunction "EN_1") (pintype "passive"))
      (node (ref "X2") (pin "4") (pinfunction "VDD_4") (pintype "passive"))
    )
    (net (code "4") (name "/A0") (class "Default")
      (node (ref "U1") (pin "R27") (pinfunction "IO_L34P_A13_M1WE_1_R27") (pintype "output+no_connect"))
    )
    (net (code "5") (name "/A1") (class "Default")
      (node (ref "U1") (pin "Y28") (pinfunction "IO_L44P_A3_M1DQ6_1_Y28") (pintype "output+no_connect"))
    )
    (net (code "6") (name "/A2") (class "Default")
      (node (ref "U1") (pin "N29") (pinfunction "IO_L29P_A23_M1A13_1_N29") (pintype "output+no_connect"))
    )
    (net (code "7") (name "/A3") (class "Default")
      (node (ref "U1") (pin "T26") (pinfunction "IO_L35P_A11_M1A7_1_T26") (pintype "output+no_connect"))
    )
    (net (code "8") (name "/A4") (class "Default")
      (node (ref "U1") (pin "P26") (pinfunction "IO_L32P_A17_M1A8_1_P26") (pintype "output+no_connect"))
    )
    (net (code "9") (name "/A9") (class "Default")
      (node (ref "U1") (pin "F25") (pinfunction "IO_L1N_A24_VREF_5_F25") (pintype "output+no_connect"))
    )
    (net (code "10") (name "/AWAKE") (class "Default")
      (node (ref "AWAKE") (pin "1") (pinfunction "In_1") (pintype "passive"))
      (node (ref "U1") (pin "AA24") (pinfunction "IO_L74P_AWAKE_1_AA24") (pintype "bidirectional"))
    )
    (net (code "11") (name "/BUSY") (class "Default")
      (node (ref "BUSY") (pin "1") (pinfunction "In_1") (pintype "passive"))
      (node (ref "U1") (pin "AA25") (pinfunction "IO_L74N_DOUT_BUSY_1_AA25") (pintype "bidirectional"))
    )
    (net (code "12") (name "/CCLK") (class "Default")
      (node (ref "CCLK") (pin "1") (pinfunction "In_1") (pintype "passive"))
      (node (ref "R46") (pin "2") (pinfunction "2_2") (pintype "passive"))
      (node (ref "R47") (pin "2") (pinfunction "2_2") (pintype "passive"))
      (node (ref "R56") (pin "2") (pinfunction "2_2") (pintype "passive"))
      (node (ref "R57") (pin "1") (pinfunction "1_1") (pintype "passive"))
      (node (ref "U1") (pin "AJ26") (pinfunction "IO_L1P_CCLK_2_AJ26") (pintype "bidirectional"))
      (node (ref "U2") (pin "12") (pinfunction "CLK_12") (pintype "input"))
      (node (ref "U3") (pin "12") (pinfunction "CLK_12") (pintype "input"))
    )
    (net (code "13") (name "/CMPCS_B") (class "Default")
      (node (ref "CMPCSB") (pin "1") (pinfunction "In_1") (pintype "passive"))
      (node (ref "U1") (pin "AC25") (pinfunction "CMPCS_B_2_AC25") (pintype "input"))
    )
    (net (code "14") (name "/CSI_B") (class "Default")
      (node (ref "R52") (pin "1") (pinfunction "1_1") (pintype "passive"))
      (node (ref "U1") (pin "AK25") (pinfunction "IO_L3N_MOSI_CSI_B_MISO0_2_AK25") (pintype "bidirectional"))
    )
    (net (code "15") (name "/CSO_B") (class "Default")
      (node (ref "CSOB") (pin "1") (pinfunction "In_1") (pintype "passive"))
      (node (ref "U1") (pin "AK6") (pinfunction "IO_L65N_CSO_B_2_AK6") (pintype "bidirectional"))
    )
    (net (code "16") (name "/D0") (class "Default")
      (node (ref "U1") (pin "AJ25") (pinfunction "IO_L3P_D0_DIN_MISO_MISO1_2_AJ25") (pintype "bidirectional"))
      (node (ref "U2") (pin "28") (pinfunction "D0_28") (pintype "tri_state"))
      (node (ref "U3") (pin "28") (pinfunction "D0_28") (pintype "tri_state"))
    )
    (net (code "17") (name "/D1") (class "Default")
      (node (ref "U1") (pin "AB20") (pinfunction "IO_L12P_D1_MISO2_2_AB20") (pintype "bidirectional"))
      (node (ref "U2") (pin "29") (pinfunction "D1_29") (pintype "tri_state"))
      (node (ref "U3") (pin "29") (pinfunction "D1_29") (pintype "tri_state"))
    )
    (net (code "18") (name "/D2") (class "Default")
      (node (ref "U1") (pin "AC20") (pinfunction "IO_L12N_D2_MISO3_2_AC20") (pintype "bidirectional"))
      (node (ref "U2") (pin "32") (pinfunction "D2_32") (pintype "tri_state"))
      (node (ref "U3") (pin "32") (pinfunction "D2_32") (pintype "tri_state"))
    )
    (net (code "19") (name "/D3") (class "Default")
      (node (ref "U1") (pin "AE11") (pinfunction "IO_L49P_D3_2_AE11") (pintype "bidirectional"))
      (node (ref "U2") (pin "33") (pinfunction "D3_33") (pintype "tri_state"))
      (node (ref "U3") (pin "33") (pinfunction "D3_33") (pintype "tri_state"))
    )
    (net (code "20") (name "/D4") (class "Default")
      (node (ref "U1") (pin "AF11") (pinfunction "IO_L49N_D4_2_AF11") (pintype "bidirectional"))
      (node (ref "U2") (pin "43") (pinfunction "D4_43") (pintype "tri_state"))
      (node (ref "U3") (pin "43") (pinfunction "D4_43") (pintype "tri_state"))
    )
    (net (code "21") (name "/D5") (class "Default")
      (node (ref "U1") (pin "AH7") (pinfunction "IO_L62P_D5_2_AH7") (pintype "bidirectional"))
      (node (ref "U2") (pin "44") (pinfunction "D5_44") (pintype "tri_state"))
      (node (ref "U3") (pin "44") (pinfunction "D5_44") (pintype "tri_state"))
    )
    (net (code "22") (name "/D6") (class "Default")
      (node (ref "U1") (pin "AK7") (pinfunction "IO_L62N_D6_2_AK7") (pintype "bidirectional"))
      (node (ref "U2") (pin "47") (pinfunction "D6_47") (pintype "tri_state"))
      (node (ref "U3") (pin "47") (pinfunction "D6_47") (pintype "tri_state"))
    )
    (net (code "23") (name "/D7") (class "Default")
      (node (ref "U1") (pin "AB13") (pinfunction "IO_L48P_D7_2_AB13") (pintype "bidirectional"))
      (node (ref "U2") (pin "48") (pinfunction "D7_48") (pintype "tri_state"))
      (node (ref "U3") (pin "48") (pinfunction "D7_48") (pintype "tri_state"))
    )
    (net (code "24") (name "/DONE") (class "Default")
      (node (ref "DONE") (pin "1") (pinfunction "In_1") (pintype "passive"))
      (node (ref "R42") (pin "2") (pinfunction "2_2") (pintype "passive"))
      (node (ref "U1") (pin "AD25") (pinfunction "DONE_2_AD25") (pintype "bidirectional"))
      (node (ref "U17") (pin "2") (pinfunction "A_2") (pintype "input"))
      (node (ref "U2") (pin "13") (pinfunction "~{CE}_13") (pintype "input"))
    )
    (net (code "25") (name "/DONE2") (class "Default")
      (node (ref "R45") (pin "1") (pinfunction "1_1") (pintype "passive"))
      (node (ref "U17") (pin "4") (pinfunction "Y_4") (pintype "open_collector"))
    )
    (net (code "26") (name "/DONE_LED") (class "Default")
      (node (ref "D1") (pin "A") (pinfunction "ANODE_A") (pintype "passive"))
      (node (ref "R45") (pin "2") (pinfunction "2_2") (pintype "passive"))
    )
    (net (code "28") (name "/HSWAPEN") (class "Default")
      (node (ref "R54") (pin "1") (pinfunction "1_1") (pintype "passive"))
      (node (ref "U1") (pin "H9") (pinfunction "IO_L1P_HSWAPEN_0_H9") (pintype "bidirectional"))
    )
    (net (code "29") (name "/INIT2") (class "Default")
      (node (ref "R59") (pin "1") (pinfunction "1_1") (pintype "passive"))
      (node (ref "U40") (pin "4") (pinfunction "Y_4") (pintype "output"))
    )
    (net (code "30") (name "/INIT_B") (class "Default")
      (node (ref "INIT") (pin "1") (pinfunction "In_1") (pintype "passive"))
      (node (ref "R43") (pin "2") (pinfunction "2_2") (pintype "passive"))
      (node (ref "U1") (pin "AJ6") (pinfunction "IO_L65P_INIT_B_2_AJ6") (pintype "bidirectional"))
      (node (ref "U2") (pin "11") (pinfunction "OE/~{RESET}_11") (pintype "bidirectional"))
      (node (ref "U3") (pin "11") (pinfunction "OE/~{RESET}_11") (pintype "bidirectional"))
      (node (ref "U40") (pin "2") (pinfunction "A_2") (pintype "input"))
    )
    (net (code "31") (name "/INIT_LED") (class "Default")
      (node (ref "D41") (pin "A") (pinfunction "ANODE_A") (pintype "passive"))
      (node (ref "R59") (pin "2") (pinfunction "2_2") (pintype "passive"))
    )
    (net (code "32") (name "/M0") (class "Default")
      (node (ref "R50") (pin "1") (pinfunction "1_1") (pintype "passive"))
      (node (ref "U1") (pin "AK26") (pinfunction "IO_L1N_M0_CMPMISO_2_AK26") (pintype "bidirectional"))
    )
    (net (code "33") (name "/M1") (class "Default")
      (node (ref "R51") (pin "1") (pinfunction "1_1") (pintype "passive"))
      (node (ref "U1") (pin "AG24") (pinfunction "IO_L13P_M1_2_AG24") (pintype "bidirectional"))
    )
    (net (code "34") (name "/POR") (class "Default")
      (node (ref "R40") (pin "2") (pinfunction "2_2") (pintype "passive"))
      (node (ref "U5") (pin "2") (pinfunction "~{RESET}_2") (pintype "open_collector"))
      (node (ref "U6") (pin "2") (pinfunction "A_2") (pintype "input"))
    )
    (net (code "35") (name "/POR_A") (class "Default")
      (node (ref "D40") (pin "A") (pinfunction "ANODE_A") (pintype "passive"))
      (node (ref "R58") (pin "2") (pinfunction "2_2") (pintype "passive"))
    )
    (net (code "36") (name "/POR_K") (class "Default")
      (node (ref "D40") (pin "K") (pinfunction "CATHODE_K") (pintype "passive"))
      (node (ref "R41") (pin "1") (pinfunction "1_1") (pintype "passive"))
      (node (ref "U6") (pin "4") (pinfunction "Y_4") (pintype "open_collector"))
    )
    (net (code "37") (name "/RDWR_B") (class "Default")
      (node (ref "R53") (pin "1") (pinfunction "1_1") (pintype "passive"))
      (node (ref "U1") (pin "AC13") (pinfunction "IO_L48N_RDWR_B_VREF_2_AC13") (pintype "bidirectional"))
    )
    (net (code "38") (name "/TCK_2V5") (class "Default")
      (node (ref "U1") (pin "H23") (pinfunction "TCK_H23") (pintype "input"))
      (node (ref "U2") (pin "20") (pinfunction "TCK_20") (pintype "input"))
      (node (ref "U3") (pin "20") (pinfunction "TCK_20") (pintype "input"))
      (node (ref "U8") (pin "4") (pinfunction "B_4") (pintype "output"))
    )
    (net (code "39") (name "/TCK_Pr") (class "Default")
      (node (ref "TCK") (pin "1") (pinfunction "In_1") (pintype "passive"))
      (node (ref "U8") (pin "3") (pinfunction "A_3") (pintype "input"))
    )
    (net (code "40") (name "/TDI_2V5") (class "Default")
      (node (ref "U1") (pin "J24") (pinfunction "TDI_J24") (pintype "input"))
      (node (ref "U7") (pin "4") (pinfunction "B_4") (pintype "output"))
    )
    (net (code "41") (name "/TDI_Pr") (class "Default")
      (node (ref "TDI") (pin "1") (pinfunction "In_1") (pintype "passive"))
      (node (ref "U7") (pin "3") (pinfunction "A_3") (pintype "input"))
    )
    (net (code "42") (name "/TDO_2V5") (class "Default")
      (node (ref "U10") (pin "4") (pinfunction "B_4") (pintype "output"))
      (node (ref "U3") (pin "22") (pinfunction "TDO_22") (pintype "output"))
    )
    (net (code "43") (name "/TDO_FPGA") (class "Default")
      (node (ref "TDOF") (pin "1") (pinfunction "In_1") (pintype "passive"))
      (node (ref "U1") (pin "H25") (pinfunction "TDO_H25") (pintype "output"))
      (node (ref "U2") (pin "19") (pinfunction "TDI_19") (pintype "input"))
    )
    (net (code "44") (name "/TDO_PROM0") (class "Default")
      (node (ref "TDOP") (pin "1") (pinfunction "In_1") (pintype "passive"))
      (node (ref "U2") (pin "22") (pinfunction "TDO_22") (pintype "output"))
      (node (ref "U3") (pin "19") (pinfunction "TDI_19") (pintype "input"))
    )
    (net (code "45") (name "/TDO_Pr") (class "Default")
      (node (ref "TDO") (pin "1") (pinfunction "In_1") (pintype "passive"))
      (node (ref "U10") (pin "3") (pinfunction "A_3") (pintype "input"))
    )
    (net (code "46") (name "/TMS_2V5") (class "Default")
      (node (ref "U1") (pin "K25") (pinfunction "TMS_K25") (pintype "input"))
      (node (ref "U2") (pin "21") (pinfunction "TMS_21") (pintype "input"))
      (node (ref "U3") (pin "21") (pinfunction "TMS_21") (pintype "input"))
      (node (ref "U9") (pin "4") (pinfunction "B_4") (pintype "output"))
    )
    (net (code "47") (name "/TMS_Pr") (class "Default")
      (node (ref "TMS") (pin "1") (pinfunction "In_1") (pintype "passive"))
      (node (ref "U9") (pin "3") (pinfunction "A_3") (pintype "input"))
    )
    (net (code "48") (name "/ck20") (class "Default")
      (node (ref "R46") (pin "1") (pinfunction "1_1") (pintype "passive"))
      (node (ref "U4") (pin "14") (pinfunction "Q0_14") (pintype "output"))
    )
    (net (code "49") (name "/ck33") (class "Default")
      (node (ref "R47") (pin "1") (pinfunction "1_1") (pintype "passive"))
      (node (ref "X2") (pin "3") (pinfunction "OUT_3") (pintype "passive"))
    )
    (net (code "50") (name "/en_ext_sel") (class "Default")
      (node (ref "R48") (pin "2") (pinfunction "2_2") (pintype "passive"))
      (node (ref "U2") (pin "25") (pinfunction "~{EN_EXT_SE}L_25") (pintype "input"))
    )
    (net (code "51") (name "/en_ext_sel_2") (class "Default")
      (node (ref "R49") (pin "2") (pinfunction "2_2") (pintype "passive"))
      (node (ref "U3") (pin "25") (pinfunction "~{EN_EXT_SE}L_25") (pintype "input"))
    )
    (net (code "52") (name "/led1") (class "Default")
      (node (ref "U1") (pin "AA29") (pinfunction "IO_L45P_A1_M1LDQS_1_AA29") (pintype "output+no_connect"))
    )
    (net (code "53") (name "/led2") (class "Default")
      (node (ref "U1") (pin "U28") (pinfunction "IO_L38N_A4_M1CLKN_1_U28") (pintype "output+no_connect"))
    )
    (net (code "54") (name "/led3") (class "Default")
      (node (ref "U1") (pin "U29") (pinfunction "IO_L37P_A7_M1A0_1_U29") (pintype "output+no_connect"))
    )
    (net (code "55") (name "/led4") (class "Default")
      (node (ref "U1") (pin "R29") (pinfunction "IO_L33P_A15_M1A10_1_R29") (pintype "output+no_connect"))
    )
    (net (code "56") (name "/led5") (class "Default")
      (node (ref "U1") (pin "AA30") (pinfunction "IO_L45N_A0_M1LDQSN_1_AA30") (pintype "output+no_connect"))
    )
    (net (code "57") (name "/led6") (class "Default")
      (node (ref "U1") (pin "U30") (pinfunction "IO_L37N_A6_M1A1_1_U30") (pintype "output+no_connect"))
    )
    (net (code "58") (name "/led7") (class "Default")
      (node (ref "U1") (pin "N27") (pinfunction "IO_L30P_A21_M1RESET_1_N27") (pintype "output+no_connect"))
    )
    (net (code "59") (name "/led8") (class "Default")
      (node (ref "U1") (pin "T27") (pinfunction "IO_L35N_A10_M1A2_1_T27") (pintype "output+no_connect"))
    )
    (net (code "60") (name "/led9") (class "Default")
      (node (ref "U1") (pin "R28") (pinfunction "IO_L34N_A12_M1BA2_1_R28") (pintype "output+no_connect"))
    )
    (net (code "61") (name "/led10") (class "Default")
      (node (ref "U1") (pin "G25") (pinfunction "IO_L1P_A25_5_G25") (pintype "output+no_connect"))
    )
    (net (code "62") (name "/led11") (class "Default")
      (node (ref "U1") (pin "Y30") (pinfunction "IO_L44N_A2_M1DQ7_1_Y30") (pintype "output+no_connect"))
    )
    (net (code "63") (name "/led12") (class "Default")
      (node (ref "U1") (pin "U27") (pinfunction "IO_L38P_A5_M1CLK_1_U27") (pintype "output+no_connect"))
    )
    (net (code "64") (name "/led13") (class "Default")
      (node (ref "U1") (pin "T28") (pinfunction "IO_L36P_A9_M1BA0_1_T28") (pintype "output+no_connect"))
    )
    (net (code "65") (name "/led14") (class "Default")
      (node (ref "U1") (pin "P30") (pinfunction "IO_L31N_A18_M1A12_1_P30") (pintype "output+no_connect"))
    )
    (net (code "66") (name "/led15") (class "Default")
      (node (ref "U1") (pin "P28") (pinfunction "IO_L31P_A19_M1CKE_1_P28") (pintype "output+no_connect"))
    )
    (net (code "67") (name "/led16") (class "Default")
      (node (ref "U1") (pin "P27") (pinfunction "IO_L32N_A16_M1A9_1_P27") (pintype "output+no_connect"))
    )
    (net (code "68") (name "/led17") (class "Default")
      (node (ref "U1") (pin "N28") (pinfunction "IO_L30N_A20_M1A11_1_N28") (pintype "output+no_connect"))
    )
    (net (code "69") (name "/led18") (class "Default")
      (node (ref "U1") (pin "T30") (pinfunction "IO_L36N_A8_M1BA1_1_T30") (pintype "output+no_connect"))
    )
    (net (code "70") (name "/led19") (class "Default")
      (node (ref "U1") (pin "R30") (pinfunction "IO_L33N_A14_M1A4_1_R30") (pintype "output+no_connect"))
    )
    (net (code "71") (name "/led20") (class "Default")
      (node (ref "U1") (pin "N30") (pinfunction "IO_L29N_A22_M1A14_1_N30") (pintype "output+no_connect"))
    )
    (net (code "73") (name "/mc_sn") (class "Default")
      (node (ref "DSN") (pin "1") (pinfunction "In_1") (pintype "passive"))
      (node (ref "R55") (pin "2") (pinfunction "2_2") (pintype "passive"))
      (node (ref "U11") (pin "2") (pinfunction "Data_2") (pintype "bidirectional"))
    )
    (net (code "74") (name "/mez_clock") (class "Default")
      (node (ref "TTCCLK") (pin "1") (pinfunction "In_1") (pintype "passive"))
      (node (ref "U4") (pin "2") (pinfunction "CLK_2") (pintype "input"))
    )
    (net (code "75") (name "/{slash}CEO") (class "Default")
      (node (ref "U2") (pin "10") (pinfunction "~{CEO}_10") (pintype "output"))
      (node (ref "U3") (pin "13") (pinfunction "~{CE}_13") (pintype "input"))
    )
    (net (code "76") (name "/{slash}CS") (class "Default")
      (node (ref "CSB") (pin "1") (pinfunction "In_1") (pintype "passive"))
      (node (ref "U1") (pin "AA27") (pinfunction "IO_L46P_FCS_B_M1DQ2_1_AA27") (pintype "bidirectional"))
    )
    (net (code "77") (name "/{slash}INIT") (class "Default")
      (node (ref "INITB") (pin "1") (pinfunction "In_1") (pintype "passive"))
      (node (ref "U1") (pin "AA28") (pinfunction "IO_L46N_FOE_B_M1DQ3_1_AA28") (pintype "bidirectional"))
    )
    (net (code "78") (name "/{slash}PROGR") (class "Default")
      (node (ref "PROGB") (pin "1") (pinfunction "In_1") (pintype "passive"))
      (node (ref "R41") (pin "2") (pinfunction "2_2") (pintype "passive"))
      (node (ref "R44") (pin "2") (pinfunction "2_2") (pintype "passive"))
      (node (ref "U1") (pin "AB8") (pinfunction "PROGRAM_B_2_AB8") (pintype "input"))
      (node (ref "U2") (pin "6") (pinfunction "~{CF}_6") (pintype "open_collector"))
      (node (ref "U3") (pin "6") (pinfunction "~{CF}_6") (pintype "open_collector"))
    )
    (net (code "79") (name "/{slash}WRITE") (class "Default")
      (node (ref "U1") (pin "Y26") (pinfunction "IO_L47P_FWE_B_M1DQ0_1_Y26") (pintype "bidirectional"))
      (node (ref "WRITEB") (pin "1") (pinfunction "In_1") (pintype "passive"))
    )
    (net (code "80") (name "GND") (class "Default")
      (node (ref "C40") (pin "2") (pinfunction "2_2") (pintype "passive"))
      (node (ref "C41") (pin "2") (pinfunction "2_2") (pintype "passive"))
      (node (ref "C42") (pin "2") (pinfunction "2_2") (pintype "passive"))
      (node (ref "C43") (pin "2") (pinfunction "2_2") (pintype "passive"))
      (node (ref "C44") (pin "2") (pinfunction "2_2") (pintype "passive"))
      (node (ref "C45") (pin "2") (pinfunction "2_2") (pintype "passive"))
      (node (ref "C46") (pin "2") (pinfunction "2_2") (pintype "passive"))
      (node (ref "C47") (pin "2") (pinfunction "2_2") (pintype "passive"))
      (node (ref "D1") (pin "K") (pinfunction "CATHODE_K") (pintype "passive"))
      (node (ref "D41") (pin "K") (pinfunction "CATHODE_K") (pintype "passive"))
      (node (ref "R48") (pin "1") (pinfunction "1_1") (pintype "passive"))
      (node (ref "R49") (pin "1") (pinfunction "1_1") (pintype "passive"))
      (node (ref "R50") (pin "2") (pinfunction "2_2") (pintype "passive"))
      (node (ref "R52") (pin "2") (pinfunction "2_2") (pintype "passive"))
      (node (ref "R53") (pin "2") (pinfunction "2_2") (pintype "passive"))
      (node (ref "R54") (pin "2") (pinfunction "2_2") (pintype "passive"))
      (node (ref "R57") (pin "2") (pinfunction "2_2") (pintype "passive"))
      (node (ref "U1") (pin "AB25") (pinfunction "SUSPEND_AB25") (pintype "input"))
      (node (ref "U1") (pin "AB26") (pinfunction "VBATT_AB26") (pintype "power_in"))
      (node (ref "U1") (pin "AB27") (pinfunction "RFUSE_AB27") (pintype "input"))
      (node (ref "U1") (pin "AF27") (pinfunction "VFS_AF27") (pintype "input"))
      (node (ref "U10") (pin "2") (pinfunction "GND_2") (pintype "power_in"))
      (node (ref "U10") (pin "5") (pinfunction "DIR_5") (pintype "input"))
      (node (ref "U11") (pin "1") (pinfunction "GND_1") (pintype "power_in"))
      (node (ref "U11") (pin "4") (pinfunction "GND_4") (pintype "power_in"))
      (node (ref "U2") (pin "17") (pinfunction "GND_17") (pintype "power_in"))
      (node (ref "U2") (pin "2") (pinfunction "GND_2") (pintype "power_in"))
      (node (ref "U2") (pin "23") (pinfunction "GND_23") (pintype "power_in"))
      (node (ref "U2") (pin "26") (pinfunction "REV_SEL0_26") (pintype "input"))
      (node (ref "U2") (pin "27") (pinfunction "REV_SEL1_27") (pintype "input"))
      (node (ref "U2") (pin "31") (pinfunction "GND_31") (pintype "power_in"))
      (node (ref "U2") (pin "36") (pinfunction "GND_36") (pintype "power_in"))
      (node (ref "U2") (pin "46") (pinfunction "GND_46") (pintype "power_in"))
      (node (ref "U2") (pin "5") (pinfunction "BUSY_5") (pintype "input"))
      (node (ref "U2") (pin "7") (pinfunction "GND_7") (pintype "power_in"))
      (node (ref "U3") (pin "17") (pinfunction "GND_17") (pintype "power_in"))
      (node (ref "U3") (pin "2") (pinfunction "GND_2") (pintype "power_in"))
      (node (ref "U3") (pin "23") (pinfunction "GND_23") (pintype "power_in"))
      (node (ref "U3") (pin "26") (pinfunction "REV_SEL0_26") (pintype "input"))
      (node (ref "U3") (pin "27") (pinfunction "REV_SEL1_27") (pintype "input"))
      (node (ref "U3") (pin "31") (pinfunction "GND_31") (pintype "power_in"))
      (node (ref "U3") (pin "36") (pinfunction "GND_36") (pintype "power_in"))
      (node (ref "U3") (pin "46") (pinfunction "GND_46") (pintype "power_in"))
      (node (ref "U3") (pin "5") (pinfunction "BUSY_5") (pintype "input"))
      (node (ref "U3") (pin "7") (pinfunction "GND_7") (pintype "power_in"))
      (node (ref "U4") (pin "3") (pinfunction "D0_3") (pintype "input"))
      (node (ref "U4") (pin "4") (pinfunction "D1_4") (pintype "input"))
      (node (ref "U4") (pin "5") (pinfunction "D2_5") (pintype "input"))
      (node (ref "U4") (pin "6") (pinfunction "D3_6") (pintype "input"))
      (node (ref "U4") (pin "8") (pinfunction "GND_8") (pintype "power_in"))
      (node (ref "U5") (pin "1") (pinfunction "GND_1") (pintype "power_in"))
      (node (ref "U5") (pin "4") (pinfunction "GND_4") (pintype "power_in"))
      (node (ref "U7") (pin "2") (pinfunction "GND_2") (pintype "power_in"))
      (node (ref "U8") (pin "2") (pinfunction "GND_2") (pintype "power_in"))
      (node (ref "U9") (pin "2") (pinfunction "GND_2") (pintype "power_in"))
      (node (ref "X2") (pin "2") (pinfunction "GND_2") (pintype "passive"))
    )
    (net (code "81") (name "unconnected-(U2-CLKOUT-Pad9)") (class "Default")
      (node (ref "U2") (pin "9") (pinfunction "CLKOUT_9") (pintype "output"))
    )
    (net (code "82") (name "unconnected-(U2-DNC1-Pad1)") (class "Default")
      (node (ref "U2") (pin "1") (pinfunction "DNC1_1") (pintype "passive"))
    )
    (net (code "83") (name "unconnected-(U2-DNC3-Pad3)") (class "Default")
      (node (ref "U2") (pin "3") (pinfunction "DNC3_3") (pintype "passive"))
    )
    (net (code "84") (name "unconnected-(U2-DNC14-Pad14)") (class "Default")
      (node (ref "U2") (pin "14") (pinfunction "DNC14_14") (pintype "passive"))
    )
    (net (code "85") (name "unconnected-(U2-DNC16-Pad16)") (class "Default")
      (node (ref "U2") (pin "16") (pinfunction "DNC16_16") (pintype "passive"))
    )
    (net (code "86") (name "unconnected-(U2-DNC18-Pad18)") (class "Default")
      (node (ref "U2") (pin "18") (pinfunction "DNC18_18") (pintype "passive"))
    )
    (net (code "87") (name "unconnected-(U2-DNC35-Pad35)") (class "Default")
      (node (ref "U2") (pin "35") (pinfunction "DNC35_35") (pintype "passive"))
    )
    (net (code "88") (name "unconnected-(U2-DNC37-Pad37)") (class "Default")
      (node (ref "U2") (pin "37") (pinfunction "DNC37_37") (pintype "passive"))
    )
    (net (code "89") (name "unconnected-(U2-DNC39-Pad39)") (class "Default")
      (node (ref "U2") (pin "39") (pinfunction "DNC39_39") (pintype "passive"))
    )
    (net (code "90") (name "unconnected-(U2-DNC40-Pad40)") (class "Default")
      (node (ref "U2") (pin "40") (pinfunction "DNC40_40") (pintype "passive"))
    )
    (net (code "91") (name "unconnected-(U2-DNC41-Pad41)") (class "Default")
      (node (ref "U2") (pin "41") (pinfunction "DNC41_41") (pintype "passive"))
    )
    (net (code "92") (name "unconnected-(U2-DNC42-Pad42)") (class "Default")
      (node (ref "U2") (pin "42") (pinfunction "DNC42_42") (pintype "passive"))
    )
    (net (code "93") (name "unconnected-(U3-CLKOUT-Pad9)") (class "Default")
      (node (ref "U3") (pin "9") (pinfunction "CLKOUT_9") (pintype "output"))
    )
    (net (code "94") (name "unconnected-(U3-DNC1-Pad1)") (class "Default")
      (node (ref "U3") (pin "1") (pinfunction "DNC1_1") (pintype "passive"))
    )
    (net (code "95") (name "unconnected-(U3-DNC3-Pad3)") (class "Default")
      (node (ref "U3") (pin "3") (pinfunction "DNC3_3") (pintype "passive"))
    )
    (net (code "96") (name "unconnected-(U3-DNC14-Pad14)") (class "Default")
      (node (ref "U3") (pin "14") (pinfunction "DNC14_14") (pintype "passive"))
    )
    (net (code "97") (name "unconnected-(U3-DNC16-Pad16)") (class "Default")
      (node (ref "U3") (pin "16") (pinfunction "DNC16_16") (pintype "passive"))
    )
    (net (code "98") (name "unconnected-(U3-DNC18-Pad18)") (class "Default")
      (node (ref "U3") (pin "18") (pinfunction "DNC18_18") (pintype "passive"))
    )
    (net (code "99") (name "unconnected-(U3-DNC35-Pad35)") (class "Default")
      (node (ref "U3") (pin "35") (pinfunction "DNC35_35") (pintype "passive"))
    )
    (net (code "100") (name "unconnected-(U3-DNC37-Pad37)") (class "Default")
      (node (ref "U3") (pin "37") (pinfunction "DNC37_37") (pintype "passive"))
    )
    (net (code "101") (name "unconnected-(U3-DNC39-Pad39)") (class "Default")
      (node (ref "U3") (pin "39") (pinfunction "DNC39_39") (pintype "passive"))
    )
    (net (code "102") (name "unconnected-(U3-DNC40-Pad40)") (class "Default")
      (node (ref "U3") (pin "40") (pinfunction "DNC40_40") (pintype "passive"))
    )
    (net (code "103") (name "unconnected-(U3-DNC41-Pad41)") (class "Default")
      (node (ref "U3") (pin "41") (pinfunction "DNC41_41") (pintype "passive"))
    )
    (net (code "104") (name "unconnected-(U3-DNC42-Pad42)") (class "Default")
      (node (ref "U3") (pin "42") (pinfunction "DNC42_42") (pintype "passive"))
    )
    (net (code "105") (name "unconnected-(U3-~{CEO}-Pad10)") (class "Default")
      (node (ref "U3") (pin "10") (pinfunction "~{CEO}_10") (pintype "output"))
    )
    (net (code "106") (name "unconnected-(U4-Q1-Pad13)") (class "Default")
      (node (ref "U4") (pin "13") (pinfunction "Q1_13") (pintype "output"))
    )
    (net (code "107") (name "unconnected-(U4-Q2-Pad12)") (class "Default")
      (node (ref "U4") (pin "12") (pinfunction "Q2_12") (pintype "output"))
    )
    (net (code "108") (name "unconnected-(U4-Q3-Pad11)") (class "Default")
      (node (ref "U4") (pin "11") (pinfunction "Q3_11") (pintype "output"))
    )
    (net (code "109") (name "unconnected-(U4-TC-Pad15)") (class "Default")
      (node (ref "U4") (pin "15") (pinfunction "TC_15") (pintype "output"))
    )
    (net (code "110") (name "unconnected-(U11-NC-Pad3)") (class "Default")
      (node (ref "U11") (pin "3") (pinfunction "NC_3") (pintype "power_in"))
    )
  )
)
